# dac.net
KiCad netlist of a schematic drawn in Altium Designer
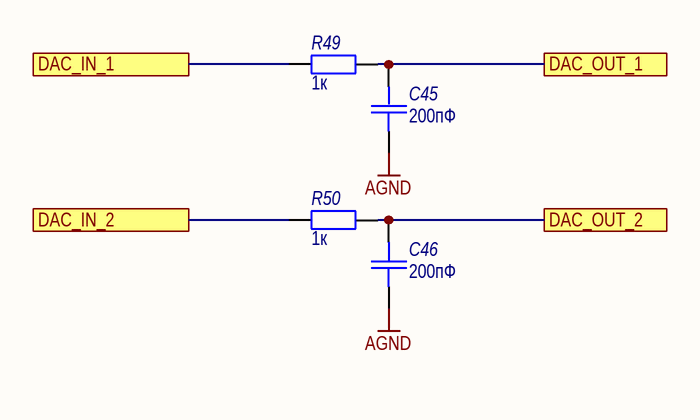
[diagram p0: dac.SchDoc]

(export (version "E")
  (design (tool "Eeschema 10.0.6"))
  (components
    (comp (ref "C45")
      (value "200пФ")
      (footprint "SMD_0805")
      (description "Capacitor")
      (libsource (lib "Passive") (part "Capacitor"))
    )
    (comp (ref "C46")
      (value "200пФ")
      (footprint "SMD_0805")
      (description "Capacitor")
      (libsource (lib "Passive") (part "Capacitor"))
    )
    (comp (ref "R49")
      (value "1к")
      (footprint "SMD_0603")
      (description "Resistor")
      (libsource (lib "Passive") (part "Resistor"))
    )
    (comp (ref "R50")
      (value "1к")
      (footprint "SMD_0603")
      (description "Resistor")
      (libsource (lib "Passive") (part "Resistor"))
    )
  )
  (nets
    (net (code "1") (name "/DAC_IN_1") (class "Default")
      (node (ref "R49") (pin "1") (pinfunction "1_1") (pintype "passive"))
    )
    (net (code "2") (name "/DAC_IN_2") (class "Default")
      (node (ref "R50") (pin "1") (pinfunction "1_1") (pintype "passive"))
    )
    (net (code "3") (name "/DAC_OUT_1") (class "Default")
      (node (ref "C45") (pin "2") (pinfunction "2_2") (pintype "passive"))
      (node (ref "R49") (pin "2") (pinfunction "2_2") (pintype "passive"))
    )
    (net (code "4") (name "/DAC_OUT_2") (class "Default")
      (node (ref "C46") (pin "2") (pinfunction "2_2") (pintype "passive"))
      (node (ref "R50") (pin "2") (pinfunction "2_2") (pintype "passive"))
    )
    (net (code "5") (name "AGND") (class "Default")
      (node (ref "C45") (pin "1") (pinfunction "1_1") (pintype "passive"))
      (node (ref "C46") (pin "1") (pinfunction "1_1") (pintype "passive"))
    )
  )
)
